# Wildfire_Souce.net
KiCad netlist of a schematic drawn in EasyEDA
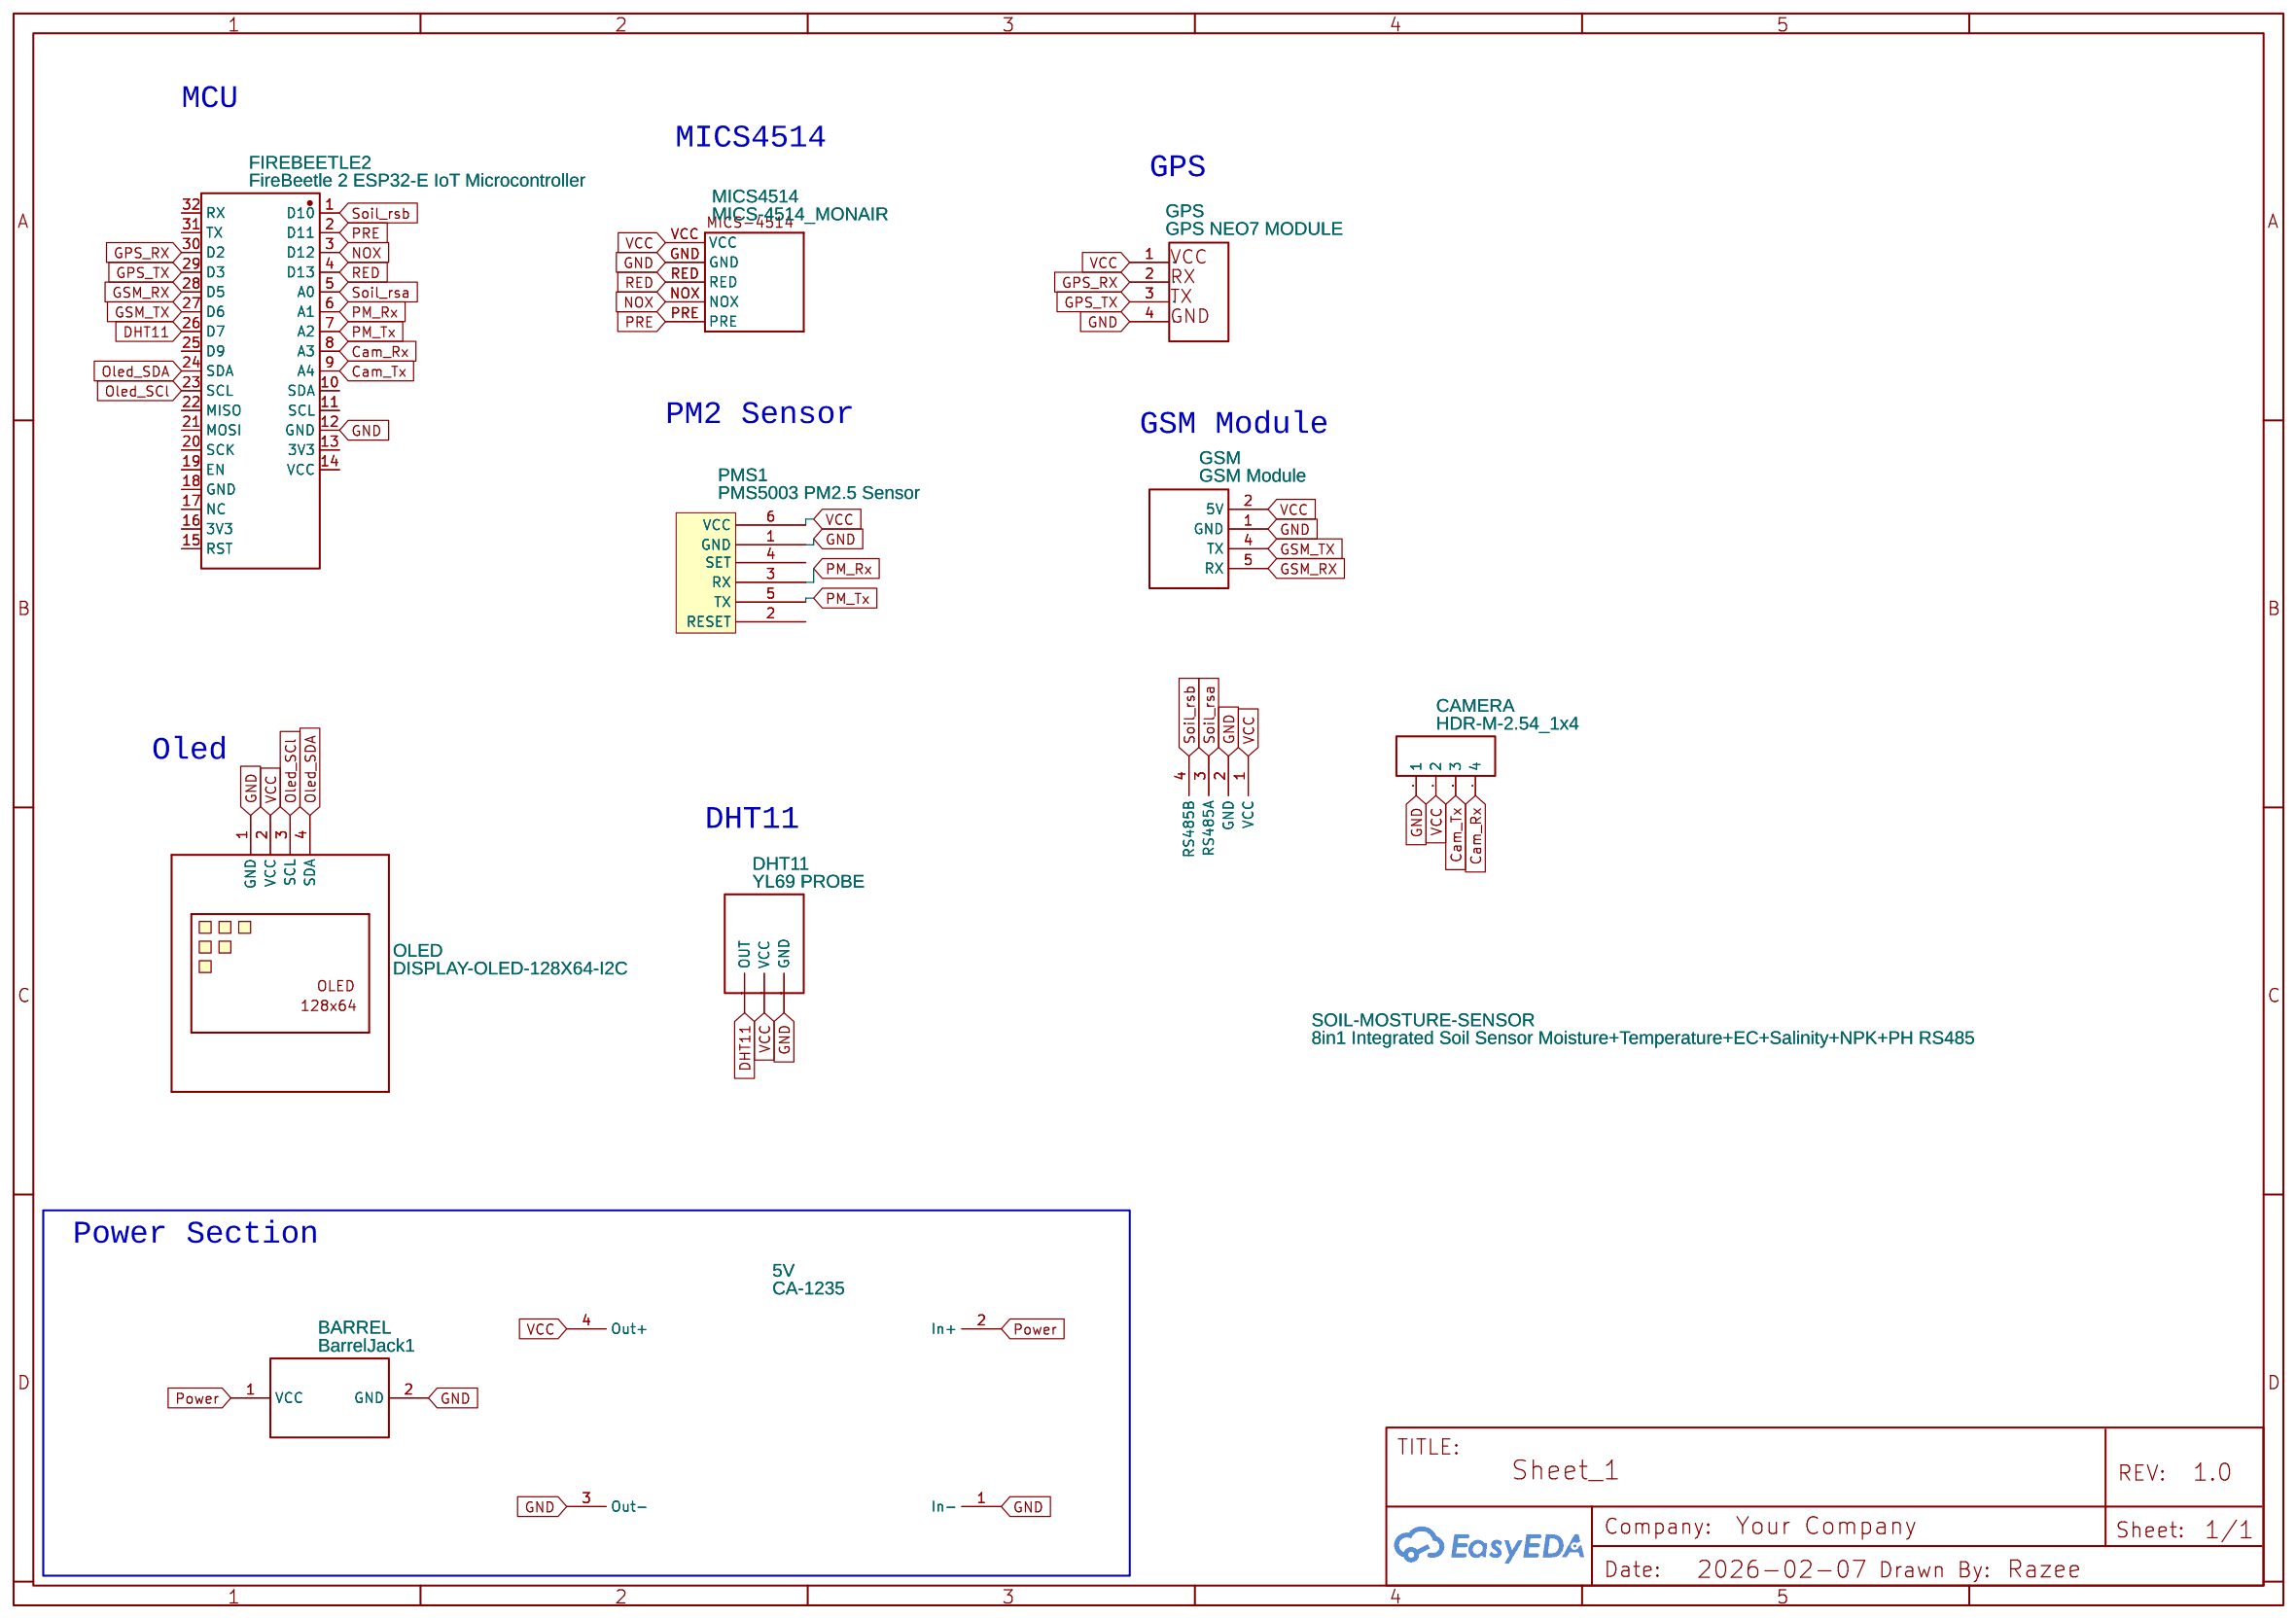
[diagram p0: schematic sheet]

(export (version "E")
  (design (tool "Eeschema 10.0.6"))
  (components
    (comp (ref "5V") (value "CA-1235") (libsource (lib "") (part "CA-1235")))
    (comp (ref "BARREL") (value "BarrelJack1") (libsource (lib "") (part "BarrelJack1")))
    (comp (ref "CAMERA") (value "HDR-M-2.54_1x4") (libsource (lib "") (part "HDR-M-2.54_1x4")))
    (comp (ref "DHT11") (value "YL69 PROBE") (libsource (lib "") (part "YL69 PROBE")))
    (comp (ref "FIREBEETLE2")
      (value "FireBeetle 2 ESP32-E IoT Microcontroller")
      (fields (field (name "Manufacturer Part") "DFR0654-F") (field (name "Manufacturer") "DFRobot"))
      (libsource (lib "") (part "FireBeetle 2 ESP32-E IoT Microcontroller"))
    )
    (comp (ref "GPS") (value "GPS NEO7 MODULE") (libsource (lib "") (part "GPS NEO7 MODULE")))
    (comp (ref "GSM") (value "GSM Module") (libsource (lib "") (part "GSM Module")))
    (comp (ref "MICS4514") (value "MICS-4514_MONAIR") (libsource (lib "") (part "MICS-4514_MONAIR")))
    (comp (ref "OLED")
      (value "DISPLAY-OLED-128X64-I2C")
      (libsource (lib "") (part "DISPLAY-OLED-128X64-I2C"))
    )
    (comp (ref "PMS1") (value "PMS5003 PM2.5 Sensor") (libsource (lib "") (part "PMS5003 PM2.5 Sensor")))
    (comp (ref "SOIL-MOSTURE-SENSOR")
      (value "8in1 Integrated Soil Sensor Moisture+Temperature+EC+Salinity+NPK+PH RS485")
      (libsource (lib "") (part "JST Connector 4 Pin"))
    )
  )
  (nets
    (net (code "1") (name "Cam_Rx") (class "Default")
      (node (ref "CAMERA") (pin "4") (pinfunction "4_4") (pintype "unspecified"))
      (node (ref "FIREBEETLE2") (pin "8") (pinfunction "A3_8") (pintype "unspecified"))
    )
    (net (code "2") (name "Cam_Tx") (class "Default")
      (node (ref "CAMERA") (pin "3") (pinfunction "3_3") (pintype "unspecified"))
      (node (ref "FIREBEETLE2") (pin "9") (pinfunction "A4_9") (pintype "unspecified"))
    )
    (net (code "3") (name "DHT11") (class "Default")
      (node (ref "DHT11") (pin "OUT") (pinfunction "OUT_OUT") (pintype "unspecified"))
      (node (ref "FIREBEETLE2") (pin "26") (pinfunction "D7_26") (pintype "unspecified"))
    )
    (net (code "4") (name "GND") (class "Default")
      (node (ref "5V") (pin "1") (pinfunction "In-_1") (pintype "input"))
      (node (ref "5V") (pin "3") (pinfunction "Out-_3") (pintype "output"))
      (node (ref "BARREL") (pin "2") (pinfunction "GND_2") (pintype "unspecified"))
      (node (ref "CAMERA") (pin "1") (pinfunction "1_1") (pintype "unspecified"))
      (node (ref "DHT11") (pin "GND") (pinfunction "GND_GND") (pintype "unspecified"))
      (node (ref "FIREBEETLE2") (pin "12") (pinfunction "GND_12") (pintype "unspecified"))
      (node (ref "GPS") (pin "4") (pinfunction "4_4") (pintype "unspecified"))
      (node (ref "GSM") (pin "1") (pinfunction "GND_1") (pintype "unspecified"))
      (node (ref "MICS4514") (pin "GND") (pinfunction "GND_GND") (pintype "bidirectional"))
      (node (ref "OLED") (pin "1") (pinfunction "GND_1") (pintype "bidirectional"))
      (node (ref "PMS1") (pin "1") (pinfunction "GND_1") (pintype "unspecified"))
      (node (ref "SOIL-MOSTURE-SENSOR") (pin "2") (pinfunction "GND_2") (pintype "unspecified"))
    )
    (net (code "5") (name "GPS_RX") (class "Default")
      (node (ref "FIREBEETLE2") (pin "30") (pinfunction "D2_30") (pintype "unspecified"))
      (node (ref "GPS") (pin "2") (pinfunction "2_2") (pintype "unspecified"))
    )
    (net (code "6") (name "GPS_TX") (class "Default")
      (node (ref "FIREBEETLE2") (pin "29") (pinfunction "D3_29") (pintype "unspecified"))
      (node (ref "GPS") (pin "3") (pinfunction "3_3") (pintype "unspecified"))
    )
    (net (code "7") (name "GSM_RX") (class "Default")
      (node (ref "FIREBEETLE2") (pin "28") (pinfunction "D5_28") (pintype "unspecified"))
      (node (ref "GSM") (pin "5") (pinfunction "RX_5") (pintype "unspecified"))
    )
    (net (code "8") (name "GSM_TX") (class "Default")
      (node (ref "FIREBEETLE2") (pin "27") (pinfunction "D6_27") (pintype "unspecified"))
      (node (ref "GSM") (pin "4") (pinfunction "TX_4") (pintype "unspecified"))
    )
    (net (code "9") (name "NOX") (class "Default")
      (node (ref "FIREBEETLE2") (pin "3") (pinfunction "D12_3") (pintype "unspecified"))
      (node (ref "MICS4514") (pin "NOX") (pinfunction "NOX_NOX") (pintype "bidirectional"))
    )
    (net (code "10") (name "Oled_SCl") (class "Default")
      (node (ref "FIREBEETLE2") (pin "23") (pinfunction "SCL_23") (pintype "unspecified"))
      (node (ref "OLED") (pin "3") (pinfunction "SCL_3") (pintype "bidirectional"))
    )
    (net (code "11") (name "Oled_SDA") (class "Default")
      (node (ref "FIREBEETLE2") (pin "24") (pinfunction "SDA_24") (pintype "unspecified"))
      (node (ref "OLED") (pin "4") (pinfunction "SDA_4") (pintype "bidirectional"))
    )
    (net (code "12") (name "PM_Rx") (class "Default")
      (node (ref "FIREBEETLE2") (pin "6") (pinfunction "A1_6") (pintype "unspecified"))
      (node (ref "PMS1") (pin "3") (pinfunction "RX_3") (pintype "unspecified"))
    )
    (net (code "13") (name "PM_Tx") (class "Default")
      (node (ref "FIREBEETLE2") (pin "7") (pinfunction "A2_7") (pintype "unspecified"))
      (node (ref "PMS1") (pin "5") (pinfunction "TX_5") (pintype "unspecified"))
    )
    (net (code "14") (name "PRE") (class "Default")
      (node (ref "FIREBEETLE2") (pin "2") (pinfunction "D11_2") (pintype "unspecified"))
      (node (ref "MICS4514") (pin "PRE") (pinfunction "PRE_PRE") (pintype "bidirectional"))
    )
    (net (code "15") (name "Power") (class "Default")
      (node (ref "5V") (pin "2") (pinfunction "In+_2") (pintype "input"))
      (node (ref "BARREL") (pin "1") (pinfunction "VCC_1") (pintype "unspecified"))
    )
    (net (code "16") (name "RED") (class "Default")
      (node (ref "FIREBEETLE2") (pin "4") (pinfunction "D13_4") (pintype "unspecified"))
      (node (ref "MICS4514") (pin "RED") (pinfunction "RED_RED") (pintype "bidirectional"))
    )
    (net (code "17") (name "Soil_rsa") (class "Default")
      (node (ref "FIREBEETLE2") (pin "5") (pinfunction "A0_5") (pintype "unspecified"))
      (node (ref "SOIL-MOSTURE-SENSOR") (pin "3") (pinfunction "RS485A_3") (pintype "unspecified"))
    )
    (net (code "18") (name "Soil_rsb") (class "Default")
      (node (ref "FIREBEETLE2") (pin "1") (pinfunction "D10_1") (pintype "unspecified"))
      (node (ref "SOIL-MOSTURE-SENSOR") (pin "4") (pinfunction "RS485B_4") (pintype "unspecified"))
    )
    (net (code "19") (name "VCC") (class "Default")
      (node (ref "5V") (pin "4") (pinfunction "Out+_4") (pintype "output"))
      (node (ref "CAMERA") (pin "2") (pinfunction "2_2") (pintype "unspecified"))
      (node (ref "DHT11") (pin "VCC") (pinfunction "VCC_VCC") (pintype "unspecified"))
      (node (ref "GPS") (pin "1") (pinfunction "1_1") (pintype "unspecified"))
      (node (ref "GSM") (pin "2") (pinfunction "5V_2") (pintype "unspecified"))
      (node (ref "MICS4514") (pin "VCC") (pinfunction "VCC_VCC") (pintype "bidirectional"))
      (node (ref "OLED") (pin "2") (pinfunction "VCC_2") (pintype "bidirectional"))
      (node (ref "PMS1") (pin "6") (pinfunction "VCC_6") (pintype "unspecified"))
      (node (ref "SOIL-MOSTURE-SENSOR") (pin "1") (pinfunction "VCC_1") (pintype "unspecified"))
    )
    (net (code "20") (name "unconnected-(FIREBEETLE2-3V3-Pad13)") (class "Default")
      (node (ref "FIREBEETLE2") (pin "13") (pinfunction "3V3_13") (pintype "unspecified"))
    )
    (net (code "21") (name "unconnected-(FIREBEETLE2-3V3-Pad16)") (class "Default")
      (node (ref "FIREBEETLE2") (pin "16") (pinfunction "3V3_16") (pintype "unspecified"))
    )
    (net (code "22") (name "unconnected-(FIREBEETLE2-D9-Pad25)") (class "Default")
      (node (ref "FIREBEETLE2") (pin "25") (pinfunction "D9_25") (pintype "unspecified"))
    )
    (net (code "23") (name "unconnected-(FIREBEETLE2-EN-Pad19)") (class "Default")
      (node (ref "FIREBEETLE2") (pin "19") (pinfunction "EN_19") (pintype "unspecified"))
    )
    (net (code "24") (name "unconnected-(FIREBEETLE2-GND-Pad18)") (class "Default")
      (node (ref "FIREBEETLE2") (pin "18") (pinfunction "GND_18") (pintype "unspecified"))
    )
    (net (code "25") (name "unconnected-(FIREBEETLE2-MISO-Pad22)") (class "Default")
      (node (ref "FIREBEETLE2") (pin "22") (pinfunction "MISO_22") (pintype "unspecified"))
    )
    (net (code "26") (name "unconnected-(FIREBEETLE2-MOSI-Pad21)") (class "Default")
      (node (ref "FIREBEETLE2") (pin "21") (pinfunction "MOSI_21") (pintype "unspecified"))
    )
    (net (code "27") (name "unconnected-(FIREBEETLE2-NC-Pad17)") (class "Default")
      (node (ref "FIREBEETLE2") (pin "17") (pinfunction "NC_17") (pintype "unspecified"))
    )
    (net (code "28") (name "unconnected-(FIREBEETLE2-RST-Pad15)") (class "Default")
      (node (ref "FIREBEETLE2") (pin "15") (pinfunction "RST_15") (pintype "unspecified"))
    )
    (net (code "29") (name "unconnected-(FIREBEETLE2-RX-Pad32)") (class "Default")
      (node (ref "FIREBEETLE2") (pin "32") (pinfunction "RX_32") (pintype "unspecified"))
    )
    (net (code "30") (name "unconnected-(FIREBEETLE2-SCK-Pad20)") (class "Default")
      (node (ref "FIREBEETLE2") (pin "20") (pinfunction "SCK_20") (pintype "unspecified"))
    )
    (net (code "31") (name "unconnected-(FIREBEETLE2-SCL-Pad11)") (class "Default")
      (node (ref "FIREBEETLE2") (pin "11") (pinfunction "SCL_11") (pintype "unspecified"))
    )
    (net (code "32") (name "unconnected-(FIREBEETLE2-SDA-Pad10)") (class "Default")
      (node (ref "FIREBEETLE2") (pin "10") (pinfunction "SDA_10") (pintype "unspecified"))
    )
    (net (code "33") (name "unconnected-(FIREBEETLE2-TX-Pad31)") (class "Default")
      (node (ref "FIREBEETLE2") (pin "31") (pinfunction "TX_31") (pintype "unspecified"))
    )
    (net (code "34") (name "unconnected-(FIREBEETLE2-VCC-Pad14)") (class "Default")
      (node (ref "FIREBEETLE2") (pin "14") (pinfunction "VCC_14") (pintype "unspecified"))
    )
    (net (code "35") (name "unconnected-(PMS1-RESET-Pad2)") (class "Default")
      (node (ref "PMS1") (pin "2") (pinfunction "RESET_2") (pintype "unspecified"))
    )
    (net (code "36") (name "unconnected-(PMS1-SET-Pad4)") (class "Default")
      (node (ref "PMS1") (pin "4") (pinfunction "SET_4") (pintype "unspecified"))
    )
  )
)
